# untitled.net
KiCad netlist of a schematic drawn in EAGLE
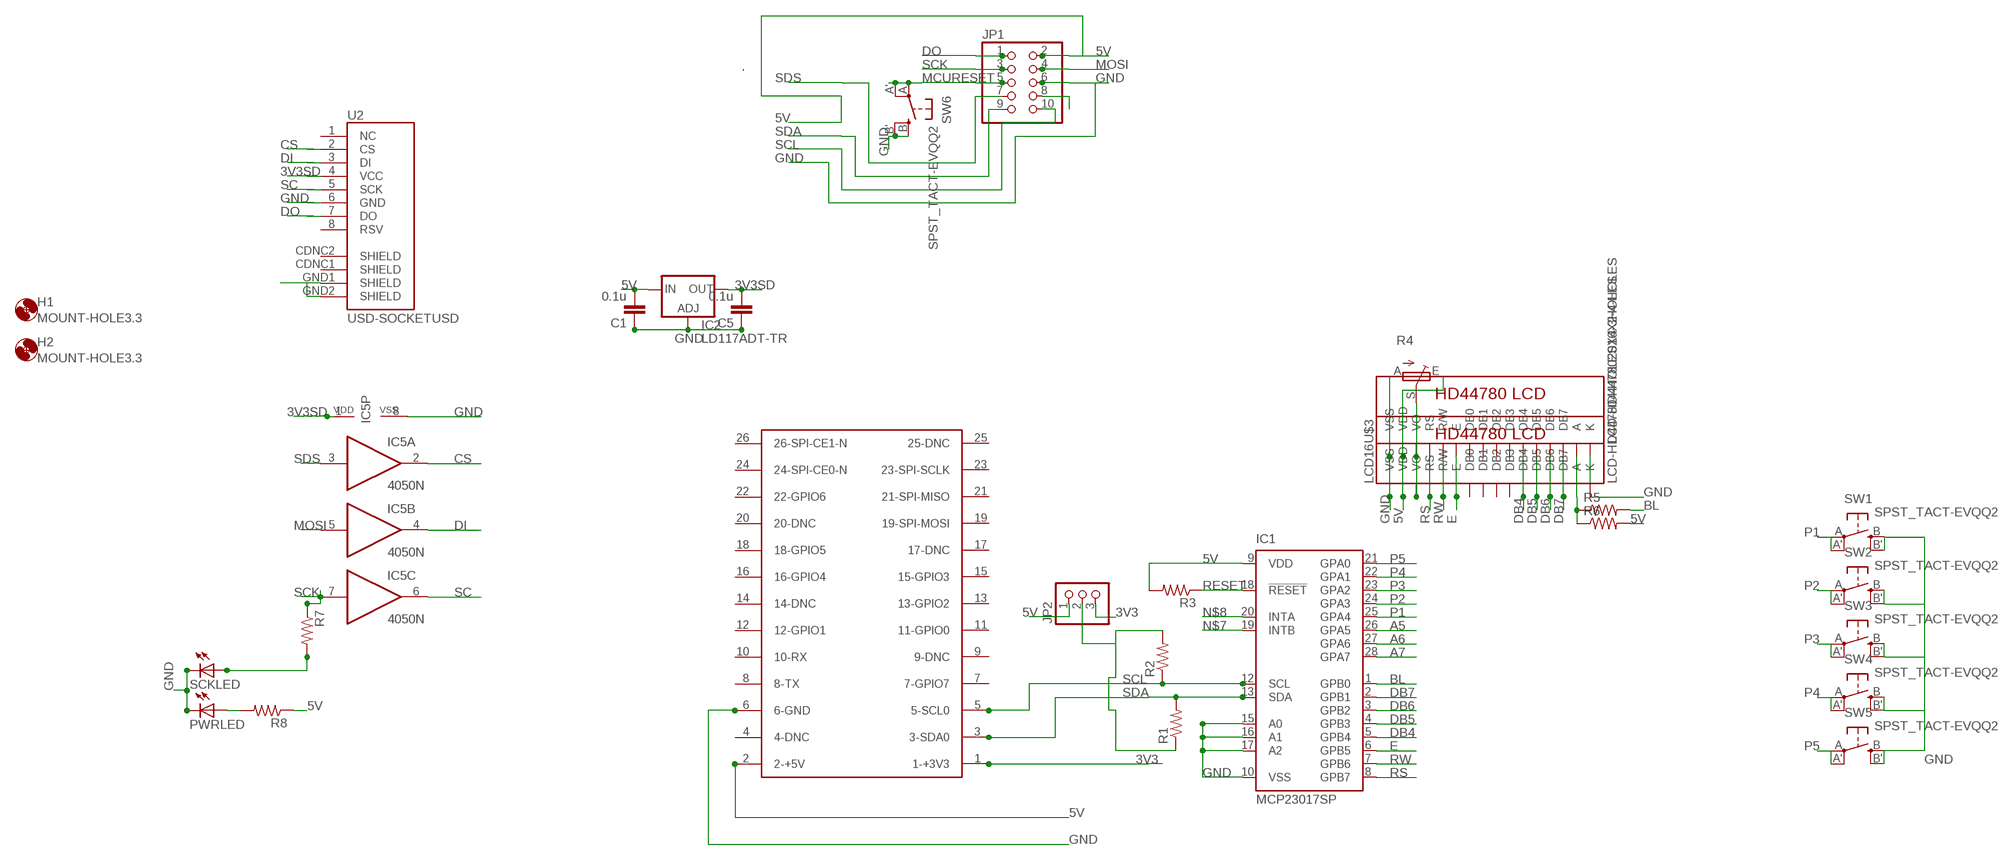
[diagram p0: schematic, sheet 1]

(export (version "E")
  (design (tool "Eeschema 10.0.6"))
  (components
    (comp (ref "C1")
      (value "0.1u")
      (footprint "eagle-import:CAP-PTH-SMALL-KIT")
      (libsource (lib "eagle-import") (part "CAPKIT"))
    )
    (comp (ref "C5")
      (value "0.1u")
      (footprint "eagle-import:CAP-PTH-SMALL-KIT")
      (libsource (lib "eagle-import") (part "CAPKIT"))
    )
    (comp (ref "H1")
      (value "MOUNT-HOLE3.3")
      (footprint "eagle-import:3,3")
      (libsource (lib "eagle-import") (part "MOUNT-HOLE3.3"))
    )
    (comp (ref "H2")
      (value "MOUNT-HOLE3.3")
      (footprint "eagle-import:3,3")
      (libsource (lib "eagle-import") (part "MOUNT-HOLE3.3"))
    )
    (comp (ref "IC1")
      (value "MCP23017SP")
      (footprint "eagle-import:DIL28-3")
      (libsource (lib "eagle-import") (part "MCP23017SP"))
    )
    (comp (ref "IC2")
      (value "LD117ADT-TR")
      (footprint "eagle-import:DPACK")
      (libsource (lib "eagle-import") (part "LD117A?DT-TR"))
    )
    (comp (ref "IC5")
      (value "4050N")
      (footprint "eagle-import:DIL16")
      (libsource (lib "eagle-import") (part "4050N"))
    )
    (comp (ref "JP1")
      (value "PINHD-2X5")
      (footprint "eagle-import:2X05")
      (libsource (lib "eagle-import") (part "PINHD-2X5"))
    )
    (comp (ref "JP2")
      (value "PINHD-1X3")
      (footprint "eagle-import:1X03")
      (libsource (lib "eagle-import") (part "PINHD-1X3"))
    )
    (comp (ref "LCD16")
      (value "LCD-HD447804-HOLES16X2-4-HOLES")
      (footprint "eagle-import:LCD-16X2-4HOLES")
      (libsource (lib "eagle-import") (part "LCD-HD4478016X2-4-HOLES4-HOLES"))
    )
    (comp (ref "PWRLED")
      (value "LED1206")
      (footprint "eagle-import:LED-1206")
      (libsource (lib "eagle-import") (part "LED1206"))
    )
    (comp (ref "R1")
      (value "R-US_0204/7")
      (footprint "eagle-import:0204_7")
      (libsource (lib "eagle-import") (part "R-US_0204/7"))
    )
    (comp (ref "R2")
      (value "R-US_0204/7")
      (footprint "eagle-import:0204_7")
      (libsource (lib "eagle-import") (part "R-US_0204/7"))
    )
    (comp (ref "R3")
      (value "R-US_0204/7")
      (footprint "eagle-import:0204_7")
      (libsource (lib "eagle-import") (part "R-US_0204/7"))
    )
    (comp (ref "R4")
      (value "TRIM_EU-CA6V")
      (footprint "eagle-import:CA6V")
      (libsource (lib "eagle-import") (part "TRIM_EU-CA6V"))
    )
    (comp (ref "R5")
      (value "R-US_0204/7")
      (footprint "eagle-import:0204_7")
      (libsource (lib "eagle-import") (part "R-US_0204/7"))
    )
    (comp (ref "R6")
      (value "R-US_0204/7")
      (footprint "eagle-import:0204_7")
      (libsource (lib "eagle-import") (part "R-US_0204/7"))
    )
    (comp (ref "R7")
      (value "R-US_0204/7")
      (footprint "eagle-import:0204_7")
      (libsource (lib "eagle-import") (part "R-US_0204/7"))
    )
    (comp (ref "R8")
      (value "R-US_0204/7")
      (footprint "eagle-import:0204_7")
      (libsource (lib "eagle-import") (part "R-US_0204/7"))
    )
    (comp (ref "SCKLED")
      (value "LED1206")
      (footprint "eagle-import:LED-1206")
      (libsource (lib "eagle-import") (part "LED1206"))
    )
    (comp (ref "SW1")
      (value "SPST_TACT-EVQQ2")
      (footprint "eagle-import:EVQ-Q2")
      (libsource (lib "eagle-import") (part "SPST_TACT-EVQQ2"))
    )
    (comp (ref "SW2")
      (value "SPST_TACT-EVQQ2")
      (footprint "eagle-import:EVQ-Q2")
      (libsource (lib "eagle-import") (part "SPST_TACT-EVQQ2"))
    )
    (comp (ref "SW3")
      (value "SPST_TACT-EVQQ2")
      (footprint "eagle-import:EVQ-Q2")
      (libsource (lib "eagle-import") (part "SPST_TACT-EVQQ2"))
    )
    (comp (ref "SW4")
      (value "SPST_TACT-EVQQ2")
      (footprint "eagle-import:EVQ-Q2")
      (libsource (lib "eagle-import") (part "SPST_TACT-EVQQ2"))
    )
    (comp (ref "SW5")
      (value "SPST_TACT-EVQQ2")
      (footprint "eagle-import:EVQ-Q2")
      (libsource (lib "eagle-import") (part "SPST_TACT-EVQQ2"))
    )
    (comp (ref "SW6")
      (value "SPST_TACT-EVQQ2")
      (footprint "eagle-import:EVQ-Q2")
      (libsource (lib "eagle-import") (part "SPST_TACT-EVQQ2"))
    )
    (comp (ref "U$2")
      (value "RASPBERRY-PI")
      (footprint "eagle-import:RASPBERRY-PI")
      (libsource (lib "eagle-import") (part "RASPBERRY-PI"))
    )
    (comp (ref "U$3")
      (value "LCD-HD4478020X4-3HOLES")
      (footprint "eagle-import:LCD-20X4-3HOLES")
      (libsource (lib "eagle-import") (part "LCD-HD4478020X4-3HOLES"))
    )
    (comp (ref "U2")
      (value "USD-SOCKETUSD")
      (footprint "eagle-import:USD-SOCKET-PP")
      (libsource (lib "eagle-import") (part "USD-SOCKETUSD"))
    )
  )
  (nets
    (net (code "1") (name "/3V3") (class "Default")
      (node (ref "JP2") (pin "3") (pinfunction "3_3") (pintype "passive"))
      (node (ref "U$2") (pin "1") (pinfunction "1-+3V3_1") (pintype "bidirectional"))
    )
    (net (code "2") (name "/3V3SD") (class "Default")
      (node (ref "C5") (pin "2") (pinfunction "2_2") (pintype "passive"))
      (node (ref "IC2") (pin "4") (pinfunction "OUT_4") (pintype "passive"))
      (node (ref "IC5") (pin "1") (pinfunction "VDD_1") (pintype "power_in"))
      (node (ref "U2") (pin "4") (pinfunction "VCC_4") (pintype "bidirectional"))
    )
    (net (code "3") (name "/5V") (class "Default")
      (node (ref "C1") (pin "2") (pinfunction "2_2") (pintype "passive"))
      (node (ref "IC1") (pin "9") (pinfunction "VDD_9") (pintype "power_in"))
      (node (ref "IC2") (pin "3") (pinfunction "IN_3") (pintype "input"))
      (node (ref "JP1") (pin "2") (pinfunction "2_2") (pintype "passive"))
      (node (ref "JP2") (pin "1") (pinfunction "1_1") (pintype "passive"))
      (node (ref "LCD16") (pin "2") (pinfunction "VDD_2") (pintype "power_in"))
      (node (ref "R3") (pin "2") (pinfunction "2_2") (pintype "passive"))
      (node (ref "R4") (pin "E") (pinfunction "E_E") (pintype "passive"))
      (node (ref "R6") (pin "2") (pinfunction "2_2") (pintype "passive"))
      (node (ref "R8") (pin "1") (pinfunction "1_1") (pintype "passive"))
      (node (ref "U$2") (pin "2") (pinfunction "2-+5V_2") (pintype "bidirectional"))
      (node (ref "U$3") (pin "P$2") (pinfunction "VDD_P$2") (pintype "power_in"))
    )
    (net (code "4") (name "/A5") (class "Default")
      (node (ref "IC1") (pin "26") (pinfunction "GPA5_26") (pintype "bidirectional"))
    )
    (net (code "5") (name "/A6") (class "Default")
      (node (ref "IC1") (pin "27") (pinfunction "GPA6_27") (pintype "bidirectional"))
    )
    (net (code "6") (name "/A7") (class "Default")
      (node (ref "IC1") (pin "28") (pinfunction "GPA7_28") (pintype "bidirectional"))
    )
    (net (code "7") (name "/BL") (class "Default")
      (node (ref "IC1") (pin "1") (pinfunction "GPB0_1") (pintype "bidirectional"))
      (node (ref "R5") (pin "2") (pinfunction "2_2") (pintype "passive"))
    )
    (net (code "8") (name "/CS") (class "Default")
      (node (ref "IC5") (pin "2") (pinfunction "O_2") (pintype "output"))
      (node (ref "U2") (pin "2") (pinfunction "CS_2") (pintype "bidirectional"))
    )
    (net (code "9") (name "/DB4") (class "Default")
      (node (ref "IC1") (pin "5") (pinfunction "GPB4_5") (pintype "bidirectional"))
      (node (ref "LCD16") (pin "11") (pinfunction "DB4_11") (pintype "bidirectional"))
      (node (ref "U$3") (pin "P$11") (pinfunction "DB4_P$11") (pintype "bidirectional"))
    )
    (net (code "10") (name "/DB5") (class "Default")
      (node (ref "IC1") (pin "4") (pinfunction "GPB3_4") (pintype "bidirectional"))
      (node (ref "LCD16") (pin "12") (pinfunction "DB5_12") (pintype "bidirectional"))
      (node (ref "U$3") (pin "P$12") (pinfunction "DB5_P$12") (pintype "bidirectional"))
    )
    (net (code "11") (name "/DB6") (class "Default")
      (node (ref "IC1") (pin "3") (pinfunction "GPB2_3") (pintype "bidirectional"))
      (node (ref "LCD16") (pin "13") (pinfunction "DB6_13") (pintype "bidirectional"))
      (node (ref "U$3") (pin "P$13") (pinfunction "DB6_P$13") (pintype "bidirectional"))
    )
    (net (code "12") (name "/DB7") (class "Default")
      (node (ref "IC1") (pin "2") (pinfunction "GPB1_2") (pintype "bidirectional"))
      (node (ref "LCD16") (pin "14") (pinfunction "DB7_14") (pintype "bidirectional"))
      (node (ref "U$3") (pin "P$14") (pinfunction "DB7_P$14") (pintype "bidirectional"))
    )
    (net (code "13") (name "/DI") (class "Default")
      (node (ref "IC5") (pin "4") (pinfunction "O_4") (pintype "output"))
      (node (ref "U2") (pin "3") (pinfunction "DI_3") (pintype "bidirectional"))
    )
    (net (code "14") (name "/DO") (class "Default")
      (node (ref "JP1") (pin "1") (pinfunction "1_1") (pintype "passive"))
      (node (ref "U2") (pin "7") (pinfunction "DO_7") (pintype "bidirectional"))
    )
    (net (code "15") (name "/E") (class "Default")
      (node (ref "IC1") (pin "6") (pinfunction "GPB5_6") (pintype "bidirectional"))
      (node (ref "LCD16") (pin "6") (pinfunction "E_6") (pintype "input"))
      (node (ref "U$3") (pin "P$6") (pinfunction "E_P$6") (pintype "input"))
    )
    (net (code "16") (name "/GND") (class "Default")
      (node (ref "C1") (pin "1") (pinfunction "1_1") (pintype "passive"))
      (node (ref "C5") (pin "1") (pinfunction "1_1") (pintype "passive"))
      (node (ref "IC1") (pin "10") (pinfunction "VSS_10") (pintype "power_in"))
      (node (ref "IC1") (pin "15") (pinfunction "A0_15") (pintype "input"))
      (node (ref "IC1") (pin "16") (pinfunction "A1_16") (pintype "input"))
      (node (ref "IC1") (pin "17") (pinfunction "A2_17") (pintype "input"))
      (node (ref "IC2") (pin "1") (pinfunction "ADJ_1") (pintype "input"))
      (node (ref "IC5") (pin "8") (pinfunction "VSS_8") (pintype "power_in"))
      (node (ref "JP1") (pin "6") (pinfunction "6_6") (pintype "passive"))
      (node (ref "LCD16") (pin "1") (pinfunction "VSS_1") (pintype "power_in"))
      (node (ref "LCD16") (pin "16") (pinfunction "K_16") (pintype "power_in"))
      (node (ref "PWRLED") (pin "C") (pinfunction "C_C") (pintype "passive"))
      (node (ref "R4") (pin "A") (pinfunction "A_A") (pintype "passive"))
      (node (ref "SCKLED") (pin "C") (pinfunction "C_C") (pintype "passive"))
      (node (ref "SW1") (pin "B") (pinfunction "S_B") (pintype "passive"))
      (node (ref "SW1") (pin "B'") (pinfunction "S1_B'") (pintype "passive"))
      (node (ref "SW2") (pin "B") (pinfunction "S_B") (pintype "passive"))
      (node (ref "SW2") (pin "B'") (pinfunction "S1_B'") (pintype "passive"))
      (node (ref "SW3") (pin "B") (pinfunction "S_B") (pintype "passive"))
      (node (ref "SW3") (pin "B'") (pinfunction "S1_B'") (pintype "passive"))
      (node (ref "SW4") (pin "B") (pinfunction "S_B") (pintype "passive"))
      (node (ref "SW4") (pin "B'") (pinfunction "S1_B'") (pintype "passive"))
      (node (ref "SW5") (pin "B") (pinfunction "S_B") (pintype "passive"))
      (node (ref "SW5") (pin "B'") (pinfunction "S1_B'") (pintype "passive"))
      (node (ref "SW6") (pin "B") (pinfunction "S_B") (pintype "passive"))
      (node (ref "SW6") (pin "B'") (pinfunction "S1_B'") (pintype "passive"))
      (node (ref "U$2") (pin "6") (pinfunction "6-GND_6") (pintype "bidirectional"))
      (node (ref "U$3") (pin "P$1") (pinfunction "VSS_P$1") (pintype "power_in"))
      (node (ref "U2") (pin "6") (pinfunction "GND_6") (pintype "bidirectional"))
      (node (ref "U2") (pin "GND1") (pinfunction "SHIELD_GND1") (pintype "bidirectional"))
      (node (ref "U2") (pin "GND2") (pinfunction "SHIELD_GND2") (pintype "bidirectional"))
    )
    (net (code "17") (name "/MCURESET") (class "Default")
      (node (ref "JP1") (pin "5") (pinfunction "5_5") (pintype "passive"))
      (node (ref "SW6") (pin "A") (pinfunction "P_A") (pintype "passive"))
      (node (ref "SW6") (pin "A'") (pinfunction "P1_A'") (pintype "passive"))
    )
    (net (code "18") (name "/MOSI") (class "Default")
      (node (ref "IC5") (pin "5") (pinfunction "I_5") (pintype "input"))
      (node (ref "JP1") (pin "4") (pinfunction "4_4") (pintype "passive"))
    )
    (net (code "19") (name "/N$7") (class "Default")
      (node (ref "IC1") (pin "19") (pinfunction "INTB_19") (pintype "output"))
    )
    (net (code "20") (name "/N$8") (class "Default")
      (node (ref "IC1") (pin "20") (pinfunction "INTA_20") (pintype "output"))
    )
    (net (code "21") (name "/P1") (class "Default")
      (node (ref "IC1") (pin "25") (pinfunction "GPA4_25") (pintype "bidirectional"))
      (node (ref "SW1") (pin "A") (pinfunction "P_A") (pintype "passive"))
      (node (ref "SW1") (pin "A'") (pinfunction "P1_A'") (pintype "passive"))
    )
    (net (code "22") (name "/P2") (class "Default")
      (node (ref "IC1") (pin "24") (pinfunction "GPA3_24") (pintype "bidirectional"))
      (node (ref "SW2") (pin "A") (pinfunction "P_A") (pintype "passive"))
      (node (ref "SW2") (pin "A'") (pinfunction "P1_A'") (pintype "passive"))
    )
    (net (code "23") (name "/P3") (class "Default")
      (node (ref "IC1") (pin "23") (pinfunction "GPA2_23") (pintype "bidirectional"))
      (node (ref "SW3") (pin "A") (pinfunction "P_A") (pintype "passive"))
      (node (ref "SW3") (pin "A'") (pinfunction "P1_A'") (pintype "passive"))
    )
    (net (code "24") (name "/P4") (class "Default")
      (node (ref "IC1") (pin "22") (pinfunction "GPA1_22") (pintype "bidirectional"))
      (node (ref "SW4") (pin "A") (pinfunction "P_A") (pintype "passive"))
      (node (ref "SW4") (pin "A'") (pinfunction "P1_A'") (pintype "passive"))
    )
    (net (code "25") (name "/P5") (class "Default")
      (node (ref "IC1") (pin "21") (pinfunction "GPA0_21") (pintype "bidirectional"))
      (node (ref "SW5") (pin "A") (pinfunction "P_A") (pintype "passive"))
      (node (ref "SW5") (pin "A'") (pinfunction "P1_A'") (pintype "passive"))
    )
    (net (code "26") (name "/RESET") (class "Default")
      (node (ref "IC1") (pin "18") (pinfunction "~{RESET}_18") (pintype "input"))
      (node (ref "R3") (pin "1") (pinfunction "1_1") (pintype "passive"))
    )
    (net (code "27") (name "/RS") (class "Default")
      (node (ref "IC1") (pin "8") (pinfunction "GPB7_8") (pintype "bidirectional"))
      (node (ref "LCD16") (pin "4") (pinfunction "RS_4") (pintype "input"))
      (node (ref "U$3") (pin "P$4") (pinfunction "RS_P$4") (pintype "input"))
    )
    (net (code "28") (name "/RW") (class "Default")
      (node (ref "IC1") (pin "7") (pinfunction "GPB6_7") (pintype "bidirectional"))
      (node (ref "LCD16") (pin "5") (pinfunction "R/W_5") (pintype "input"))
      (node (ref "U$3") (pin "P$5") (pinfunction "R/W_P$5") (pintype "input"))
    )
    (net (code "29") (name "/SC") (class "Default")
      (node (ref "IC5") (pin "6") (pinfunction "O_6") (pintype "output"))
      (node (ref "U2") (pin "5") (pinfunction "SCK_5") (pintype "bidirectional"))
    )
    (net (code "30") (name "/SCK") (class "Default")
      (node (ref "IC5") (pin "7") (pinfunction "I_7") (pintype "input"))
      (node (ref "JP1") (pin "3") (pinfunction "3_3") (pintype "passive"))
      (node (ref "R7") (pin "1") (pinfunction "1_1") (pintype "passive"))
    )
    (net (code "31") (name "/SCL") (class "Default")
      (node (ref "IC1") (pin "12") (pinfunction "SCL_12") (pintype "input"))
      (node (ref "JP1") (pin "10") (pinfunction "10_10") (pintype "passive"))
      (node (ref "R2") (pin "1") (pinfunction "1_1") (pintype "passive"))
      (node (ref "U$2") (pin "5") (pinfunction "5-SCL0_5") (pintype "bidirectional"))
    )
    (net (code "32") (name "/SDA") (class "Default")
      (node (ref "IC1") (pin "13") (pinfunction "SDA_13") (pintype "bidirectional"))
      (node (ref "JP1") (pin "9") (pinfunction "9_9") (pintype "passive"))
      (node (ref "R1") (pin "2") (pinfunction "2_2") (pintype "passive"))
      (node (ref "U$2") (pin "3") (pinfunction "3-SDA0_3") (pintype "bidirectional"))
    )
    (net (code "33") (name "/SDS") (class "Default")
      (node (ref "IC5") (pin "3") (pinfunction "I_3") (pintype "input"))
      (node (ref "JP1") (pin "7") (pinfunction "7_7") (pintype "passive"))
    )
    (net (code "34") (name "Net-(JP2-Pad2)") (class "Default")
      (node (ref "JP2") (pin "2") (pinfunction "2_2") (pintype "passive"))
      (node (ref "R1") (pin "1") (pinfunction "1_1") (pintype "passive"))
      (node (ref "R2") (pin "2") (pinfunction "2_2") (pintype "passive"))
    )
    (net (code "35") (name "Net-(LCD16-A)") (class "Default")
      (node (ref "LCD16") (pin "15") (pinfunction "A_15") (pintype "power_in"))
      (node (ref "R5") (pin "1") (pinfunction "1_1") (pintype "passive"))
      (node (ref "R6") (pin "1") (pinfunction "1_1") (pintype "passive"))
      (node (ref "U$3") (pin "P$15") (pinfunction "A_P$15") (pintype "power_in"))
    )
    (net (code "36") (name "Net-(LCD16-VO)") (class "Default")
      (node (ref "LCD16") (pin "3") (pinfunction "VO_3") (pintype "bidirectional"))
      (node (ref "R4") (pin "S") (pinfunction "S_S") (pintype "passive"))
      (node (ref "U$3") (pin "P$3") (pinfunction "VO_P$3") (pintype "bidirectional"))
    )
    (net (code "37") (name "Net-(PWRLED-PadA)") (class "Default")
      (node (ref "PWRLED") (pin "A") (pinfunction "A_A") (pintype "passive"))
      (node (ref "R8") (pin "2") (pinfunction "2_2") (pintype "passive"))
    )
    (net (code "38") (name "Net-(R7-Pad2)") (class "Default")
      (node (ref "R7") (pin "2") (pinfunction "2_2") (pintype "passive"))
      (node (ref "SCKLED") (pin "A") (pinfunction "A_A") (pintype "passive"))
    )
    (net (code "39") (name "unconnected-(JP1-Pad8)") (class "Default")
      (node (ref "JP1") (pin "8") (pinfunction "8_8") (pintype "passive"))
    )
    (net (code "40") (name "unconnected-(LCD16-DB0-Pad7)") (class "Default")
      (node (ref "LCD16") (pin "7") (pinfunction "DB0_7") (pintype "bidirectional"))
    )
    (net (code "41") (name "unconnected-(LCD16-DB1-Pad8)") (class "Default")
      (node (ref "LCD16") (pin "8") (pinfunction "DB1_8") (pintype "bidirectional"))
    )
    (net (code "42") (name "unconnected-(LCD16-DB2-Pad9)") (class "Default")
      (node (ref "LCD16") (pin "9") (pinfunction "DB2_9") (pintype "bidirectional"))
    )
    (net (code "43") (name "unconnected-(LCD16-DB3-Pad10)") (class "Default")
      (node (ref "LCD16") (pin "10") (pinfunction "DB3_10") (pintype "bidirectional"))
    )
    (net (code "44") (name "unconnected-(U$2-4-DNC-Pad4)") (class "Default")
      (node (ref "U$2") (pin "4") (pinfunction "4-DNC_4") (pintype "bidirectional"))
    )
    (net (code "45") (name "unconnected-(U$2-7-GPIO7-Pad7)") (class "Default")
      (node (ref "U$2") (pin "7") (pinfunction "7-GPIO7_7") (pintype "bidirectional"))
    )
    (net (code "46") (name "unconnected-(U$2-8-TX-Pad8)") (class "Default")
      (node (ref "U$2") (pin "8") (pinfunction "8-TX_8") (pintype "bidirectional"))
    )
    (net (code "47") (name "unconnected-(U$2-9-DNC-Pad9)") (class "Default")
      (node (ref "U$2") (pin "9") (pinfunction "9-DNC_9") (pintype "bidirectional"))
    )
    (net (code "48") (name "unconnected-(U$2-10-RX-Pad10)") (class "Default")
      (node (ref "U$2") (pin "10") (pinfunction "10-RX_10") (pintype "bidirectional"))
    )
    (net (code "49") (name "unconnected-(U$2-11-GPIO0-Pad11)") (class "Default")
      (node (ref "U$2") (pin "11") (pinfunction "11-GPIO0_11") (pintype "bidirectional"))
    )
    (net (code "50") (name "unconnected-(U$2-12-GPIO1-Pad12)") (class "Default")
      (node (ref "U$2") (pin "12") (pinfunction "12-GPIO1_12") (pintype "bidirectional"))
    )
    (net (code "51") (name "unconnected-(U$2-13-GPIO2-Pad13)") (class "Default")
      (node (ref "U$2") (pin "13") (pinfunction "13-GPIO2_13") (pintype "bidirectional"))
    )
    (net (code "52") (name "unconnected-(U$2-14-DNC-Pad14)") (class "Default")
      (node (ref "U$2") (pin "14") (pinfunction "14-DNC_14") (pintype "bidirectional"))
    )
    (net (code "53") (name "unconnected-(U$2-15-GPIO3-Pad15)") (class "Default")
      (node (ref "U$2") (pin "15") (pinfunction "15-GPIO3_15") (pintype "bidirectional"))
    )
    (net (code "54") (name "unconnected-(U$2-16-GPIO4-Pad16)") (class "Default")
      (node (ref "U$2") (pin "16") (pinfunction "16-GPIO4_16") (pintype "bidirectional"))
    )
    (net (code "55") (name "unconnected-(U$2-17-DNC-Pad17)") (class "Default")
      (node (ref "U$2") (pin "17") (pinfunction "17-DNC_17") (pintype "bidirectional"))
    )
    (net (code "56") (name "unconnected-(U$2-18-GPIO5-Pad18)") (class "Default")
      (node (ref "U$2") (pin "18") (pinfunction "18-GPIO5_18") (pintype "bidirectional"))
    )
    (net (code "57") (name "unconnected-(U$2-19-SPI-MOSI-Pad19)") (class "Default")
      (node (ref "U$2") (pin "19") (pinfunction "19-SPI-MOSI_19") (pintype "bidirectional"))
    )
    (net (code "58") (name "unconnected-(U$2-20-DNC-Pad20)") (class "Default")
      (node (ref "U$2") (pin "20") (pinfunction "20-DNC_20") (pintype "bidirectional"))
    )
    (net (code "59") (name "unconnected-(U$2-21-SPI-MISO-Pad21)") (class "Default")
      (node (ref "U$2") (pin "21") (pinfunction "21-SPI-MISO_21") (pintype "bidirectional"))
    )
    (net (code "60") (name "unconnected-(U$2-22-GPIO6-Pad22)") (class "Default")
      (node (ref "U$2") (pin "22") (pinfunction "22-GPIO6_22") (pintype "bidirectional"))
    )
    (net (code "61") (name "unconnected-(U$2-23-SPI-SCLK-Pad23)") (class "Default")
      (node (ref "U$2") (pin "23") (pinfunction "23-SPI-SCLK_23") (pintype "bidirectional"))
    )
    (net (code "62") (name "unconnected-(U$2-24-SPI-CE0-N-Pad24)") (class "Default")
      (node (ref "U$2") (pin "24") (pinfunction "24-SPI-CE0-N_24") (pintype "bidirectional"))
    )
    (net (code "63") (name "unconnected-(U$2-25-DNC-Pad25)") (class "Default")
      (node (ref "U$2") (pin "25") (pinfunction "25-DNC_25") (pintype "bidirectional"))
    )
    (net (code "64") (name "unconnected-(U$2-26-SPI-CE1-N-Pad26)") (class "Default")
      (node (ref "U$2") (pin "26") (pinfunction "26-SPI-CE1-N_26") (pintype "bidirectional"))
    )
    (net (code "65") (name "unconnected-(U$3-DB0-PadP$7)") (class "Default")
      (node (ref "U$3") (pin "P$7") (pinfunction "DB0_P$7") (pintype "bidirectional"))
    )
    (net (code "66") (name "unconnected-(U$3-DB1-PadP$8)") (class "Default")
      (node (ref "U$3") (pin "P$8") (pinfunction "DB1_P$8") (pintype "bidirectional"))
    )
    (net (code "67") (name "unconnected-(U$3-DB2-PadP$9)") (class "Default")
      (node (ref "U$3") (pin "P$9") (pinfunction "DB2_P$9") (pintype "bidirectional"))
    )
    (net (code "68") (name "unconnected-(U$3-DB3-PadP$10)") (class "Default")
      (node (ref "U$3") (pin "P$10") (pinfunction "DB3_P$10") (pintype "bidirectional"))
    )
    (net (code "69") (name "unconnected-(U$3-K-PadP$16)") (class "Default")
      (node (ref "U$3") (pin "P$16") (pinfunction "K_P$16") (pintype "power_in"))
    )
    (net (code "70") (name "unconnected-(U2-NC-Pad1)") (class "Default")
      (node (ref "U2") (pin "1") (pinfunction "NC_1") (pintype "bidirectional"))
    )
    (net (code "71") (name "unconnected-(U2-RSV-Pad8)") (class "Default")
      (node (ref "U2") (pin "8") (pinfunction "RSV_8") (pintype "bidirectional"))
    )
    (net (code "72") (name "unconnected-(U2-SHIELD-PadCDNC1)") (class "Default")
      (node (ref "U2") (pin "CDNC1") (pinfunction "SHIELD_CDNC1") (pintype "bidirectional"))
    )
    (net (code "73") (name "unconnected-(U2-SHIELD-PadCDNC2)") (class "Default")
      (node (ref "U2") (pin "CDNC2") (pinfunction "SHIELD_CDNC2") (pintype "bidirectional"))
    )
  )
)
